# 21_Camera_MIPI_CSI_schdoc.net
KiCad netlist of a schematic drawn in Altium Designer
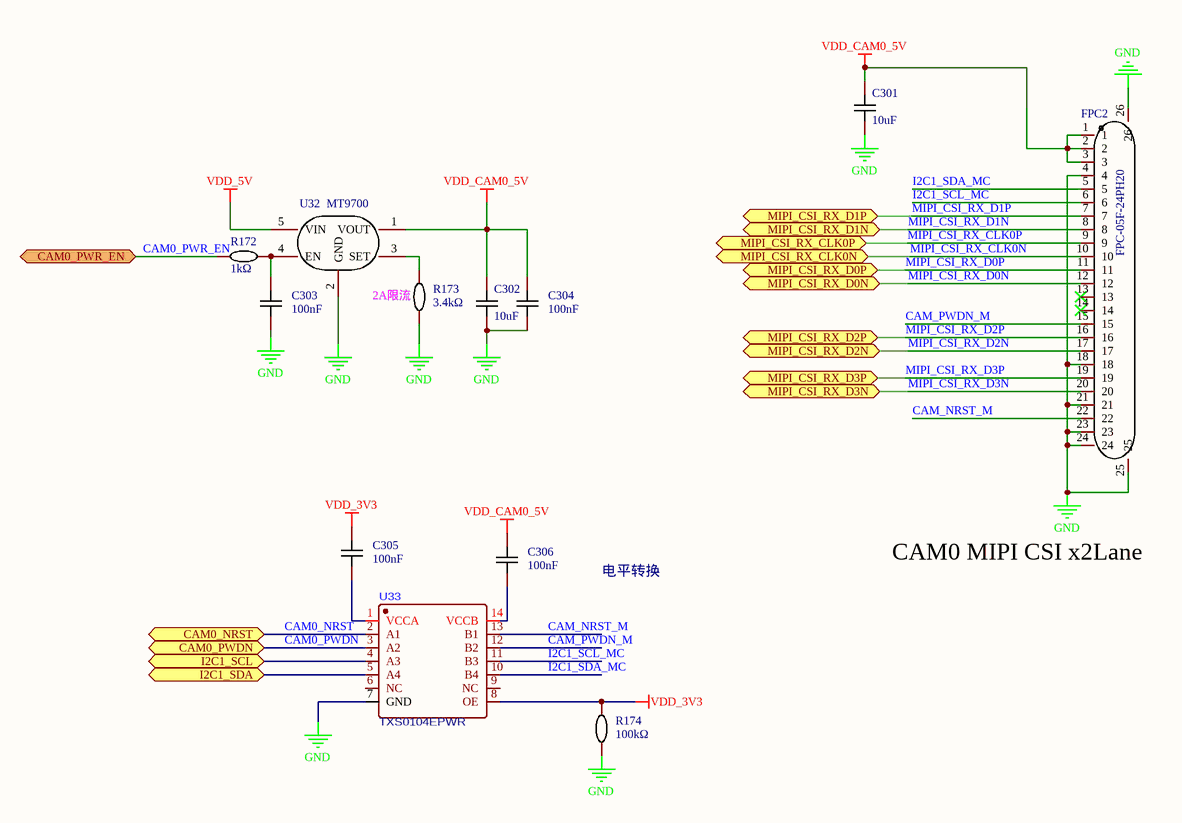
[diagram p0: 21_Camera MIPI CSI.schdoc.schdoc]

(export (version "E")
  (design (tool "Eeschema 10.0.6"))
  (components
    (comp (ref "C301")
      (value "10uF")
      (footprint "C0603")
      (fields
        (field (name "NAME") "10uF")
        (field (name "MANUFACTURER") "SAMSUNG(三星)")
        (field (name "MANUFACTURER PART") "CL10A106KP8NNNC")
        (field (name "TOLERANCE") "±10%")
      )
      (libsource (lib "altium-import") (part "root_1_CL10A106KP8NNNC_"))
    )
    (comp (ref "C302")
      (value "10uF")
      (footprint "C0603")
      (fields
        (field (name "NAME") "10uF")
        (field (name "MANUFACTURER") "SAMSUNG(三星)")
        (field (name "MANUFACTURER PART") "CL10A106KP8NNNC")
        (field (name "TOLERANCE") "±10%")
      )
      (libsource (lib "altium-import") (part "root_1_CL10A106KP8NNNC_"))
    )
    (comp (ref "C303")
      (value "100nF")
      (footprint "C0603")
      (fields
        (field (name "NAME") "100nF")
        (field (name "MANUFACTURER") "YAGEO(国巨)")
        (field (name "MANUFACTURER PART") "CC0603KRX7R9BB104")
        (field (name "TOLERANCE") "±10%")
      )
      (libsource (lib "altium-import") (part "root_1_CC0603KRX7R9BB104_"))
    )
    (comp (ref "C304")
      (value "100nF")
      (footprint "C0603")
      (fields
        (field (name "NAME") "100nF")
        (field (name "MANUFACTURER") "YAGEO(国巨)")
        (field (name "MANUFACTURER PART") "CC0603KRX7R9BB104")
        (field (name "TOLERANCE") "±10%")
      )
      (libsource (lib "altium-import") (part "root_1_CC0603KRX7R9BB104_"))
    )
    (comp (ref "C305")
      (value "100nF")
      (footprint "C0603")
      (fields
        (field (name "NAME") "100nF")
        (field (name "MANUFACTURER") "YAGEO(国巨)")
        (field (name "MANUFACTURER PART") "CC0603KRX7R9BB104")
        (field (name "TOLERANCE") "±10%")
      )
      (libsource (lib "altium-import") (part "root_1_CC0603KRX7R9BB104_"))
    )
    (comp (ref "C306")
      (value "100nF")
      (footprint "C0603")
      (fields
        (field (name "NAME") "100nF")
        (field (name "MANUFACTURER") "YAGEO(国巨)")
        (field (name "MANUFACTURER PART") "CC0603KRX7R9BB104")
        (field (name "TOLERANCE") "±10%")
      )
      (libsource (lib "altium-import") (part "root_1_CC0603KRX7R9BB104_"))
    )
    (comp (ref "FPC2")
      (value "FPC-05F-24PH20")
      (footprint "FPC-SMD_24P-P0.50_FPC-05F-24PH20")
      (fields (field (name "NAME") "FPC-05F-24PH20") (field (name "MANUFACTURER") "XUNPU(讯普)"))
      (libsource (lib "altium-import") (part "root_0_FPC-05F-24PH20_"))
    )
    (comp (ref "R172")
      (value "1kΩ")
      (footprint "R0603")
      (fields
        (field (name "NAME") "1kΩ")
        (field (name "MANUFACTURER") "YAGEO(国巨)")
        (field (name "MANUFACTURER PART") "RC0603FR-071KL")
        (field (name "TOLERANCE") "±1%")
      )
      (libsource (lib "altium-import") (part "root_0_RC0603FR-071KL_"))
    )
    (comp (ref "R173")
      (value "3.4kΩ")
      (footprint "R0603")
      (fields
        (field (name "NAME") "3.4kΩ")
        (field (name "MANUFACTURER") "UNI-ROYAL(厚声)")
        (field (name "MANUFACTURER PART") "0603WAF3401T5E")
        (field (name "TOLERANCE") "±1%")
      )
      (libsource (lib "altium-import") (part "root_1_0603WAF3401T5E_"))
    )
    (comp (ref "R174")
      (value "100kΩ")
      (footprint "R0603")
      (fields
        (field (name "NAME") "100kΩ")
        (field (name "MANUFACTURER") "UNI-ROYAL(厚声)")
        (field (name "MANUFACTURER PART") "0603WAF1003T5E")
        (field (name "TOLERANCE") "±1%")
      )
      (libsource (lib "altium-import") (part "root_1_0603WAF1003T5E_"))
    )
    (comp (ref "U32")
      (value "MT9700")
      (footprint "SOT-23-5_L3.0-W1.7-P0.95-LS2.8-BR")
      (fields (field (name "NAME") "MT9700") (field (name "MANUFACTURER") "西安航天民芯"))
      (libsource (lib "altium-import") (part "root_0_mirrored_MT9700_"))
    )
    (comp (ref "U33")
      (value "TXS0104EPWR")
      (footprint "TSSOP-14_L5.0-W4.4-P0.65-LS6.4-BL")
      (libsource (lib "RK3568核心板") (part "TXS0104EPWR"))
    )
  )
  (nets
    (net (code "1") (name "/CAM0_NRST") (class "Default")
      (node (ref "U33") (pin "2") (pinfunction "A1_2") (pintype "passive"))
    )
    (net (code "2") (name "/CAM0_PWDN") (class "Default")
      (node (ref "U33") (pin "3") (pinfunction "A2_3") (pintype "passive"))
    )
    (net (code "3") (name "/CAM0_PWR_EN") (class "Default")
      (node (ref "R172") (pin "1") (pinfunction "1_1") (pintype "passive"))
    )
    (net (code "4") (name "/CAM_NRST_M") (class "Default")
      (node (ref "FPC2") (pin "22") (pinfunction "22_22") (pintype "passive"))
      (node (ref "U33") (pin "13") (pinfunction "B1_13") (pintype "passive"))
    )
    (net (code "5") (name "/CAM_PWDN_M") (class "Default")
      (node (ref "FPC2") (pin "15") (pinfunction "15_15") (pintype "passive"))
      (node (ref "U33") (pin "12") (pinfunction "B2_12") (pintype "passive"))
    )
    (net (code "6") (name "/I2C1_SCL") (class "Default")
      (node (ref "U33") (pin "4") (pinfunction "A3_4") (pintype "passive"))
    )
    (net (code "7") (name "/I2C1_SCL_MC") (class "Default")
      (node (ref "FPC2") (pin "6") (pinfunction "6_6") (pintype "passive"))
      (node (ref "U33") (pin "11") (pinfunction "B3_11") (pintype "passive"))
    )
    (net (code "8") (name "/I2C1_SDA") (class "Default")
      (node (ref "U33") (pin "5") (pinfunction "A4_5") (pintype "passive"))
    )
    (net (code "9") (name "/I2C1_SDA_MC") (class "Default")
      (node (ref "FPC2") (pin "5") (pinfunction "5_5") (pintype "passive"))
      (node (ref "U33") (pin "10") (pinfunction "B4_10") (pintype "passive"))
    )
    (net (code "10") (name "/MIPI_CSI_RX_CLK0N") (class "Default")
      (node (ref "FPC2") (pin "10") (pinfunction "10_10") (pintype "passive"))
    )
    (net (code "11") (name "/MIPI_CSI_RX_CLK0P") (class "Default")
      (node (ref "FPC2") (pin "9") (pinfunction "9_9") (pintype "passive"))
    )
    (net (code "12") (name "/MIPI_CSI_RX_D0N") (class "Default")
      (node (ref "FPC2") (pin "12") (pinfunction "12_12") (pintype "passive"))
    )
    (net (code "13") (name "/MIPI_CSI_RX_D0P") (class "Default")
      (node (ref "FPC2") (pin "11") (pinfunction "11_11") (pintype "passive"))
    )
    (net (code "14") (name "/MIPI_CSI_RX_D1N") (class "Default")
      (node (ref "FPC2") (pin "8") (pinfunction "8_8") (pintype "passive"))
    )
    (net (code "15") (name "/MIPI_CSI_RX_D1P") (class "Default")
      (node (ref "FPC2") (pin "7") (pinfunction "7_7") (pintype "passive"))
    )
    (net (code "16") (name "/MIPI_CSI_RX_D2N") (class "Default")
      (node (ref "FPC2") (pin "17") (pinfunction "17_17") (pintype "passive"))
    )
    (net (code "17") (name "/MIPI_CSI_RX_D2P") (class "Default")
      (node (ref "FPC2") (pin "16") (pinfunction "16_16") (pintype "passive"))
    )
    (net (code "18") (name "/MIPI_CSI_RX_D3N") (class "Default")
      (node (ref "FPC2") (pin "20") (pinfunction "20_20") (pintype "passive"))
    )
    (net (code "19") (name "/MIPI_CSI_RX_D3P") (class "Default")
      (node (ref "FPC2") (pin "19") (pinfunction "19_19") (pintype "passive"))
    )
    (net (code "20") (name "GND") (class "Default")
      (node (ref "C301") (pin "1") (pinfunction "1_1") (pintype "passive"))
      (node (ref "C302") (pin "1") (pinfunction "1_1") (pintype "passive"))
      (node (ref "C303") (pin "1") (pinfunction "1_1") (pintype "passive"))
      (node (ref "C304") (pin "1") (pinfunction "1_1") (pintype "passive"))
      (node (ref "FPC2") (pin "18") (pinfunction "18_18") (pintype "passive"))
      (node (ref "FPC2") (pin "21") (pinfunction "21_21") (pintype "passive"))
      (node (ref "FPC2") (pin "23") (pinfunction "23_23") (pintype "passive"))
      (node (ref "FPC2") (pin "24") (pinfunction "24_24") (pintype "passive"))
      (node (ref "FPC2") (pin "25") (pinfunction "25_25") (pintype "passive"))
      (node (ref "FPC2") (pin "26") (pinfunction "26_26") (pintype "passive"))
      (node (ref "FPC2") (pin "4") (pinfunction "4_4") (pintype "passive"))
      (node (ref "R173") (pin "1") (pinfunction "1_1") (pintype "passive"))
      (node (ref "R174") (pin "1") (pinfunction "1_1") (pintype "passive"))
      (node (ref "U32") (pin "2") (pinfunction "GND_2") (pintype "passive"))
      (node (ref "U33") (pin "7") (pinfunction "GND_7") (pintype "passive"))
    )
    (net (code "21") (name "Net-(U32-EN)") (class "Default")
      (node (ref "C303") (pin "2") (pinfunction "2_2") (pintype "passive"))
      (node (ref "R172") (pin "2") (pinfunction "2_2") (pintype "passive"))
      (node (ref "U32") (pin "4") (pinfunction "EN_4") (pintype "passive"))
    )
    (net (code "22") (name "Net-(U32-SET)") (class "Default")
      (node (ref "R173") (pin "2") (pinfunction "2_2") (pintype "passive"))
      (node (ref "U32") (pin "3") (pinfunction "SET_3") (pintype "passive"))
    )
    (net (code "23") (name "Net-(U33-VCCA)") (class "Default")
      (node (ref "C305") (pin "1") (pinfunction "1_1") (pintype "passive"))
      (node (ref "U33") (pin "1") (pinfunction "VCCA_1") (pintype "passive"))
    )
    (net (code "24") (name "Net-(U33-VCCB)") (class "Default")
      (node (ref "C306") (pin "1") (pinfunction "1_1") (pintype "passive"))
      (node (ref "U33") (pin "14") (pinfunction "VCCB_14") (pintype "passive"))
    )
    (net (code "25") (name "VDD_3V3") (class "Default")
      (node (ref "C305") (pin "2") (pinfunction "2_2") (pintype "passive"))
      (node (ref "R174") (pin "2") (pinfunction "2_2") (pintype "passive"))
      (node (ref "U33") (pin "8") (pinfunction "OE_8") (pintype "passive"))
    )
    (net (code "26") (name "VDD_5V") (class "Default")
      (node (ref "U32") (pin "5") (pinfunction "VIN_5") (pintype "passive"))
    )
    (net (code "27") (name "VDD_CAM0_5V") (class "Default")
      (node (ref "C301") (pin "2") (pinfunction "2_2") (pintype "passive"))
      (node (ref "C302") (pin "2") (pinfunction "2_2") (pintype "passive"))
      (node (ref "C304") (pin "2") (pinfunction "2_2") (pintype "passive"))
      (node (ref "C306") (pin "2") (pinfunction "2_2") (pintype "passive"))
      (node (ref "FPC2") (pin "1") (pinfunction "1_1") (pintype "passive"))
      (node (ref "FPC2") (pin "2") (pinfunction "2_2") (pintype "passive"))
      (node (ref "FPC2") (pin "3") (pinfunction "3_3") (pintype "passive"))
      (node (ref "U32") (pin "1") (pinfunction "VOUT_1") (pintype "passive"))
    )
    (net (code "28") (name "unconnected-(FPC2-Pad13)") (class "Default")
      (node (ref "FPC2") (pin "13") (pinfunction "13_13") (pintype "passive+no_connect"))
    )
    (net (code "29") (name "unconnected-(FPC2-Pad14)") (class "Default")
      (node (ref "FPC2") (pin "14") (pinfunction "14_14") (pintype "passive+no_connect"))
    )
    (net (code "30") (name "unconnected-(U33-NC-Pad6)") (class "Default")
      (node (ref "U33") (pin "6") (pinfunction "NC_6") (pintype "passive"))
    )
    (net (code "31") (name "unconnected-(U33-NC-Pad9)") (class "Default")
      (node (ref "U33") (pin "9") (pinfunction "NC_9") (pintype "passive"))
    )
  )
)
